# DigitalClock_SCHEMATICFile_Hnit_20230223.net
KiCad netlist of a schematic drawn in Altium Designer
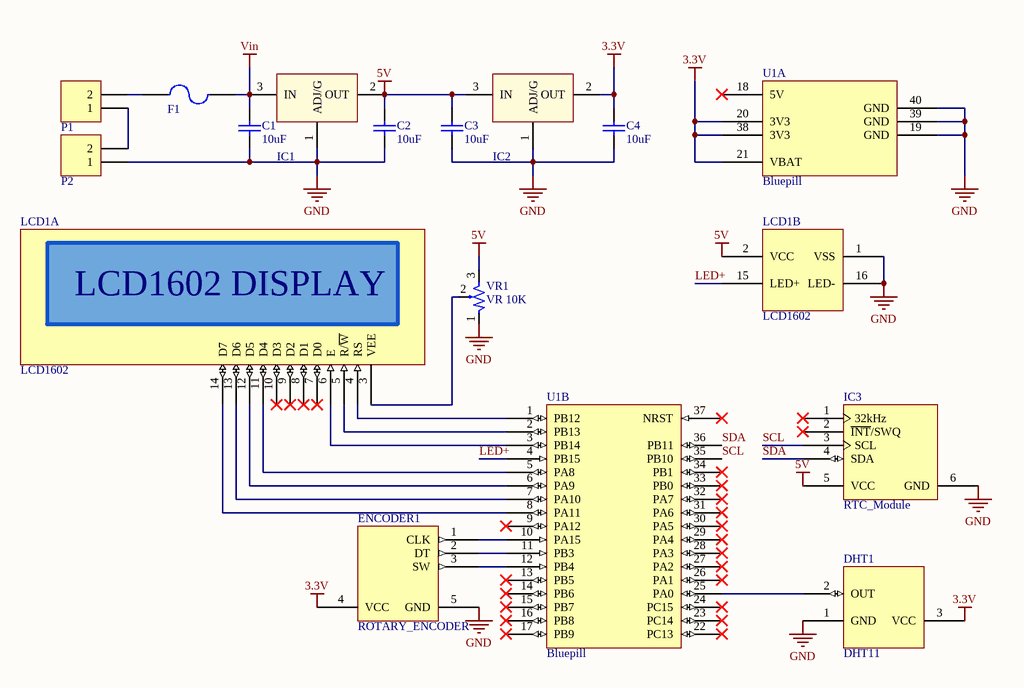
[diagram p0: DigitalClock_SCHEMATICFile_Hnit_20230223.SchDoc]

(export (version "E")
  (design (tool "Eeschema 10.0.6"))
  (components
    (comp (ref "C1")
      (value "10uF")
      (footprint "CN1")
      (description "Capacitor")
      (fields (field (name "Comment") "Cap Non-Pol"))
      (libsource (lib "PIF_Library") (part "Cap Non-Pol"))
    )
    (comp (ref "C2")
      (value "10uF")
      (footprint "CN1")
      (description "Capacitor")
      (fields (field (name "Comment") "Cap Non-Pol"))
      (libsource (lib "PIF_Library") (part "Cap Non-Pol"))
    )
    (comp (ref "C3")
      (value "10uF")
      (footprint "CN1")
      (description "Capacitor")
      (fields (field (name "Comment") "Cap Non-Pol"))
      (libsource (lib "PIF_Library") (part "Cap Non-Pol"))
    )
    (comp (ref "C4")
      (value "10uF")
      (footprint "CN1")
      (description "Capacitor")
      (fields (field (name "Comment") "Cap Non-Pol"))
      (libsource (lib "PIF_Library") (part "Cap Non-Pol"))
    )
    (comp (ref "DHT1")
      (value "DHT11")
      (footprint "DHT11")
      (description "Temperature Humidity Sensor 16bi\r\nHumidity, Temperature Digital ±5% RH Through Hole")
      (fields (field (name "MANUFACTURER") "UNIVERSAL-SOLDER Electronics Ltd"))
      (libsource (lib "LibraryOfficial_INTEGRATEDLib_Hnit_20230222") (part "DHT11"))
    )
    (comp (ref "ENCODER1")
      (value "ROTARY_ENCODER")
      (footprint "ROTARY_ENCODER")
      (description "4 Position Wire to Board Terminal Block Horizontal with Board 0.197\" (5.00mm) Through Hole")
      (fields (field (name "MANUFACTURER") "Amphenol Anytek") (field (name "VOLTAGE") "300 V"))
      (libsource (lib "LibraryOfficial_INTEGRATEDLib_Hnit_20230222") (part "ROTARY_ENCODER"))
    )
    (comp (ref "F1") (value "Fuse") (footprint "FUSE") (libsource (lib "PIF_Library") (part "Fuse")))
    (comp (ref "IC1")
      (value "LM1117")
      (footprint "QTO-220")
      (description "Available in 1.8V, 2.5V, 2.85V, 3.3V, 5V, and  Adjustable Versions")
      (libsource (lib "PIF_Library") (part "LM1117"))
    )
    (comp (ref "IC2")
      (value "LM1117")
      (footprint "QTO-220")
      (description "Available in 1.8V, 2.5V, 2.85V, 3.3V, 5V, and  Adjustable Versions")
      (libsource (lib "PIF_Library") (part "LM1117"))
    )
    (comp (ref "IC3")
      (value "RTC_Module")
      (footprint "DS3231_PINOUT_Module")
      (description "RTC MODULE CLK/CALENDAR I2C 16SOIC")
      (fields (field (name "MANUFACTURER") "Seeed Technology Co., Ltd"))
      (libsource (lib "LibraryOfficial_INTEGRATEDLib_Hnit_20230222") (part "DS3231"))
    )
    (comp (ref "LCD1")
      (value "LCD1602")
      (footprint "LCD1602")
      (libsource (lib "LibraryOfficial_INTEGRATEDLib_Hnit_20230222") (part "LCD1602"))
    )
    (comp (ref "P1")
      (value "Domino 2")
      (footprint "DOMINO SMALL 2")
      (description "Domino, 2-Pin")
      (fields (field (name "PUBLISHER") "Altium Limited"))
      (libsource (lib "PIF_Library") (part "Domino 2"))
    )
    (comp (ref "P2")
      (value "Domino 2")
      (footprint "DOMINO SMALL 2")
      (description "Domino, 2-Pin")
      (fields (field (name "PUBLISHER") "Altium Limited"))
      (libsource (lib "PIF_Library") (part "Domino 2"))
    )
    (comp (ref "U1")
      (value "Bluepill")
      (footprint "STM32F103C8T6_PINOUT_Bluepill")
      (fields (field (name "MANUFACTURER") "STMicroelectronics"))
      (libsource (lib "LibraryOfficial_INTEGRATEDLib_Hnit_20230222") (part "STM32F103C8T6"))
    )
    (comp (ref "VR1")
      (value "VR 10K")
      (footprint "Varistor 1")
      (description "Var Resistor")
      (fields (field (name "Comment") "10K"))
      (libsource (lib "PIF_Library") (part "Var Resistor"))
    )
  )
  (nets
    (net (code "1") (name "/LED+") (class "Default")
      (node (ref "LCD1") (pin "15") (pinfunction "LED+_15") (pintype "power_in"))
      (node (ref "U1") (pin "4") (pinfunction "PB15_4") (pintype "bidirectional"))
    )
    (net (code "2") (name "/SCL") (class "Default")
      (node (ref "IC3") (pin "3") (pinfunction "SCL_3") (pintype "passive"))
      (node (ref "U1") (pin "35") (pinfunction "PB10_35") (pintype "bidirectional"))
    )
    (net (code "3") (name "/SDA") (class "Default")
      (node (ref "IC3") (pin "4") (pinfunction "SDA_4") (pintype "bidirectional"))
      (node (ref "U1") (pin "36") (pinfunction "PB11_36") (pintype "bidirectional"))
    )
    (net (code "4") (name "3.3V") (class "Default")
      (node (ref "C4") (pin "2") (pinfunction "2_2") (pintype "passive"))
      (node (ref "DHT1") (pin "3") (pinfunction "VCC_3") (pintype "power_in"))
      (node (ref "ENCODER1") (pin "4") (pinfunction "VCC_4") (pintype "power_in"))
      (node (ref "IC2") (pin "2") (pinfunction "OUT_2") (pintype "passive"))
      (node (ref "U1") (pin "20") (pinfunction "3V3_20") (pintype "power_in"))
      (node (ref "U1") (pin "21") (pinfunction "VBAT_21") (pintype "power_in"))
      (node (ref "U1") (pin "38") (pinfunction "3V3_38") (pintype "power_in"))
    )
    (net (code "5") (name "5V") (class "Default")
      (node (ref "C2") (pin "2") (pinfunction "2_2") (pintype "passive"))
      (node (ref "C3") (pin "2") (pinfunction "2_2") (pintype "passive"))
      (node (ref "IC1") (pin "2") (pinfunction "OUT_2") (pintype "passive"))
      (node (ref "IC2") (pin "3") (pinfunction "IN_3") (pintype "passive"))
      (node (ref "IC3") (pin "5") (pinfunction "VCC_5") (pintype "power_in"))
      (node (ref "LCD1") (pin "2") (pinfunction "VCC_2") (pintype "power_in"))
      (node (ref "VR1") (pin "3") (pinfunction "3_3") (pintype "passive"))
    )
    (net (code "6") (name "GND") (class "Default")
      (node (ref "C1") (pin "1") (pinfunction "1_1") (pintype "passive"))
      (node (ref "C2") (pin "1") (pinfunction "1_1") (pintype "passive"))
      (node (ref "C3") (pin "1") (pinfunction "1_1") (pintype "passive"))
      (node (ref "C4") (pin "1") (pinfunction "1_1") (pintype "passive"))
      (node (ref "DHT1") (pin "1") (pinfunction "GND_1") (pintype "power_in"))
      (node (ref "ENCODER1") (pin "5") (pinfunction "GND_5") (pintype "power_in"))
      (node (ref "IC1") (pin "1") (pinfunction "ADJ/G_1") (pintype "passive"))
      (node (ref "IC2") (pin "1") (pinfunction "ADJ/G_1") (pintype "passive"))
      (node (ref "IC3") (pin "6") (pinfunction "GND_6") (pintype "power_in"))
      (node (ref "LCD1") (pin "1") (pinfunction "VSS_1") (pintype "power_in"))
      (node (ref "LCD1") (pin "16") (pinfunction "LED-_16") (pintype "power_in"))
      (node (ref "P2") (pin "1") (pinfunction "1_1") (pintype "passive"))
      (node (ref "U1") (pin "19") (pinfunction "GND_19") (pintype "power_in"))
      (node (ref "U1") (pin "39") (pinfunction "GND_39") (pintype "power_in"))
      (node (ref "U1") (pin "40") (pinfunction "GND_40") (pintype "power_in"))
      (node (ref "VR1") (pin "1") (pinfunction "1_1") (pintype "passive"))
    )
    (net (code "7") (name "Net-(DHT1-OUT)") (class "Default")
      (node (ref "DHT1") (pin "2") (pinfunction "OUT_2") (pintype "bidirectional"))
      (node (ref "U1") (pin "25") (pinfunction "PA0_25") (pintype "bidirectional"))
    )
    (net (code "8") (name "Net-(ENCODER1-CLK)") (class "Default")
      (node (ref "ENCODER1") (pin "1") (pinfunction "CLK_1") (pintype "output"))
      (node (ref "U1") (pin "10") (pinfunction "PA15_10") (pintype "bidirectional"))
    )
    (net (code "9") (name "Net-(ENCODER1-DT)") (class "Default")
      (node (ref "ENCODER1") (pin "2") (pinfunction "DT_2") (pintype "output"))
      (node (ref "U1") (pin "11") (pinfunction "PB3_11") (pintype "bidirectional"))
    )
    (net (code "10") (name "Net-(ENCODER1-SW)") (class "Default")
      (node (ref "ENCODER1") (pin "3") (pinfunction "SW_3") (pintype "output"))
      (node (ref "U1") (pin "12") (pinfunction "PB4_12") (pintype "bidirectional"))
    )
    (net (code "11") (name "Net-(F1-Pad1)") (class "Default")
      (node (ref "F1") (pin "1") (pinfunction "1_1") (pintype "passive"))
      (node (ref "P1") (pin "2") (pinfunction "2_2") (pintype "passive"))
    )
    (net (code "12") (name "Net-(LCD1A-D4)") (class "Default")
      (node (ref "LCD1") (pin "11") (pinfunction "D4_11") (pintype "bidirectional"))
      (node (ref "U1") (pin "5") (pinfunction "PA8_5") (pintype "bidirectional"))
    )
    (net (code "13") (name "Net-(LCD1A-D5)") (class "Default")
      (node (ref "LCD1") (pin "12") (pinfunction "D5_12") (pintype "bidirectional"))
      (node (ref "U1") (pin "6") (pinfunction "PA9_6") (pintype "bidirectional"))
    )
    (net (code "14") (name "Net-(LCD1A-D6)") (class "Default")
      (node (ref "LCD1") (pin "13") (pinfunction "D6_13") (pintype "bidirectional"))
      (node (ref "U1") (pin "7") (pinfunction "PA10_7") (pintype "bidirectional"))
    )
    (net (code "15") (name "Net-(LCD1A-D7)") (class "Default")
      (node (ref "LCD1") (pin "14") (pinfunction "D7_14") (pintype "bidirectional"))
      (node (ref "U1") (pin "8") (pinfunction "PA11_8") (pintype "bidirectional"))
    )
    (net (code "16") (name "Net-(LCD1A-E)") (class "Default")
      (node (ref "LCD1") (pin "6") (pinfunction "E_6") (pintype "input"))
      (node (ref "U1") (pin "3") (pinfunction "PB14_3") (pintype "bidirectional"))
    )
    (net (code "17") (name "Net-(LCD1A-RS)") (class "Default")
      (node (ref "LCD1") (pin "4") (pinfunction "RS_4") (pintype "input"))
      (node (ref "U1") (pin "1") (pinfunction "PB12_1") (pintype "bidirectional"))
    )
    (net (code "18") (name "Net-(LCD1A-R{slash}~{W})") (class "Default")
      (node (ref "LCD1") (pin "5") (pinfunction "R/~{W}_5") (pintype "input"))
      (node (ref "U1") (pin "2") (pinfunction "PB13_2") (pintype "bidirectional"))
    )
    (net (code "19") (name "Net-(LCD1A-VEE)") (class "Default")
      (node (ref "LCD1") (pin "3") (pinfunction "VEE_3") (pintype "power_in"))
      (node (ref "VR1") (pin "2") (pinfunction "2_2") (pintype "passive"))
    )
    (net (code "20") (name "Net-(P1-Pad1)") (class "Default")
      (node (ref "P1") (pin "1") (pinfunction "1_1") (pintype "passive"))
      (node (ref "P2") (pin "2") (pinfunction "2_2") (pintype "passive"))
    )
    (net (code "21") (name "Vin") (class "Default")
      (node (ref "C1") (pin "2") (pinfunction "2_2") (pintype "passive"))
      (node (ref "F1") (pin "2") (pinfunction "2_2") (pintype "passive"))
      (node (ref "IC1") (pin "3") (pinfunction "IN_3") (pintype "passive"))
    )
    (net (code "22") (name "unconnected-(IC3-32kHz-Pad1)") (class "Default")
      (node (ref "IC3") (pin "1") (pinfunction "32kHz_1") (pintype "passive+no_connect"))
    )
    (net (code "23") (name "unconnected-(IC3-~{INT}{slash}SWQ-Pad2)") (class "Default")
      (node (ref "IC3") (pin "2") (pinfunction "~{INT}/SWQ_2") (pintype "passive+no_connect"))
    )
    (net (code "24") (name "unconnected-(LCD1A-D0-Pad7)") (class "Default")
      (node (ref "LCD1") (pin "7") (pinfunction "D0_7") (pintype "bidirectional+no_connect"))
    )
    (net (code "25") (name "unconnected-(LCD1A-D1-Pad8)") (class "Default")
      (node (ref "LCD1") (pin "8") (pinfunction "D1_8") (pintype "bidirectional+no_connect"))
    )
    (net (code "26") (name "unconnected-(LCD1A-D2-Pad9)") (class "Default")
      (node (ref "LCD1") (pin "9") (pinfunction "D2_9") (pintype "bidirectional+no_connect"))
    )
    (net (code "27") (name "unconnected-(LCD1A-D3-Pad10)") (class "Default")
      (node (ref "LCD1") (pin "10") (pinfunction "D3_10") (pintype "bidirectional+no_connect"))
    )
    (net (code "28") (name "unconnected-(U1A-5V-Pad18)") (class "Default")
      (node (ref "U1") (pin "18") (pinfunction "5V_18") (pintype "power_in+no_connect"))
    )
    (net (code "29") (name "unconnected-(U1B-NRST-Pad37)") (class "Default")
      (node (ref "U1") (pin "37") (pinfunction "NRST_37") (pintype "input+no_connect"))
    )
    (net (code "30") (name "unconnected-(U1B-PA1-Pad26)") (class "Default")
      (node (ref "U1") (pin "26") (pinfunction "PA1_26") (pintype "bidirectional+no_connect"))
    )
    (net (code "31") (name "unconnected-(U1B-PA2-Pad27)") (class "Default")
      (node (ref "U1") (pin "27") (pinfunction "PA2_27") (pintype "bidirectional+no_connect"))
    )
    (net (code "32") (name "unconnected-(U1B-PA3-Pad28)") (class "Default")
      (node (ref "U1") (pin "28") (pinfunction "PA3_28") (pintype "bidirectional+no_connect"))
    )
    (net (code "33") (name "unconnected-(U1B-PA4-Pad29)") (class "Default")
      (node (ref "U1") (pin "29") (pinfunction "PA4_29") (pintype "bidirectional+no_connect"))
    )
    (net (code "34") (name "unconnected-(U1B-PA5-Pad30)") (class "Default")
      (node (ref "U1") (pin "30") (pinfunction "PA5_30") (pintype "bidirectional+no_connect"))
    )
    (net (code "35") (name "unconnected-(U1B-PA6-Pad31)") (class "Default")
      (node (ref "U1") (pin "31") (pinfunction "PA6_31") (pintype "bidirectional+no_connect"))
    )
    (net (code "36") (name "unconnected-(U1B-PA7-Pad32)") (class "Default")
      (node (ref "U1") (pin "32") (pinfunction "PA7_32") (pintype "bidirectional+no_connect"))
    )
    (net (code "37") (name "unconnected-(U1B-PA12-Pad9)") (class "Default")
      (node (ref "U1") (pin "9") (pinfunction "PA12_9") (pintype "bidirectional+no_connect"))
    )
    (net (code "38") (name "unconnected-(U1B-PB0-Pad33)") (class "Default")
      (node (ref "U1") (pin "33") (pinfunction "PB0_33") (pintype "bidirectional+no_connect"))
    )
    (net (code "39") (name "unconnected-(U1B-PB1-Pad34)") (class "Default")
      (node (ref "U1") (pin "34") (pinfunction "PB1_34") (pintype "bidirectional+no_connect"))
    )
    (net (code "40") (name "unconnected-(U1B-PB5-Pad13)") (class "Default")
      (node (ref "U1") (pin "13") (pinfunction "PB5_13") (pintype "bidirectional+no_connect"))
    )
    (net (code "41") (name "unconnected-(U1B-PB6-Pad14)") (class "Default")
      (node (ref "U1") (pin "14") (pinfunction "PB6_14") (pintype "bidirectional+no_connect"))
    )
    (net (code "42") (name "unconnected-(U1B-PB7-Pad15)") (class "Default")
      (node (ref "U1") (pin "15") (pinfunction "PB7_15") (pintype "bidirectional+no_connect"))
    )
    (net (code "43") (name "unconnected-(U1B-PB8-Pad16)") (class "Default")
      (node (ref "U1") (pin "16") (pinfunction "PB8_16") (pintype "bidirectional+no_connect"))
    )
    (net (code "44") (name "unconnected-(U1B-PB9-Pad17)") (class "Default")
      (node (ref "U1") (pin "17") (pinfunction "PB9_17") (pintype "bidirectional+no_connect"))
    )
    (net (code "45") (name "unconnected-(U1B-PC13-Pad22)") (class "Default")
      (node (ref "U1") (pin "22") (pinfunction "PC13_22") (pintype "bidirectional+no_connect"))
    )
    (net (code "46") (name "unconnected-(U1B-PC14-Pad23)") (class "Default")
      (node (ref "U1") (pin "23") (pinfunction "PC14_23") (pintype "bidirectional+no_connect"))
    )
    (net (code "47") (name "unconnected-(U1B-PC15-Pad24)") (class "Default")
      (node (ref "U1") (pin "24") (pinfunction "PC15_24") (pintype "bidirectional+no_connect"))
    )
  )
)
